# Smartfin_Main_PCBA_Wet_Dry_Sensor.net
KiCad netlist of a schematic drawn in Altium Designer
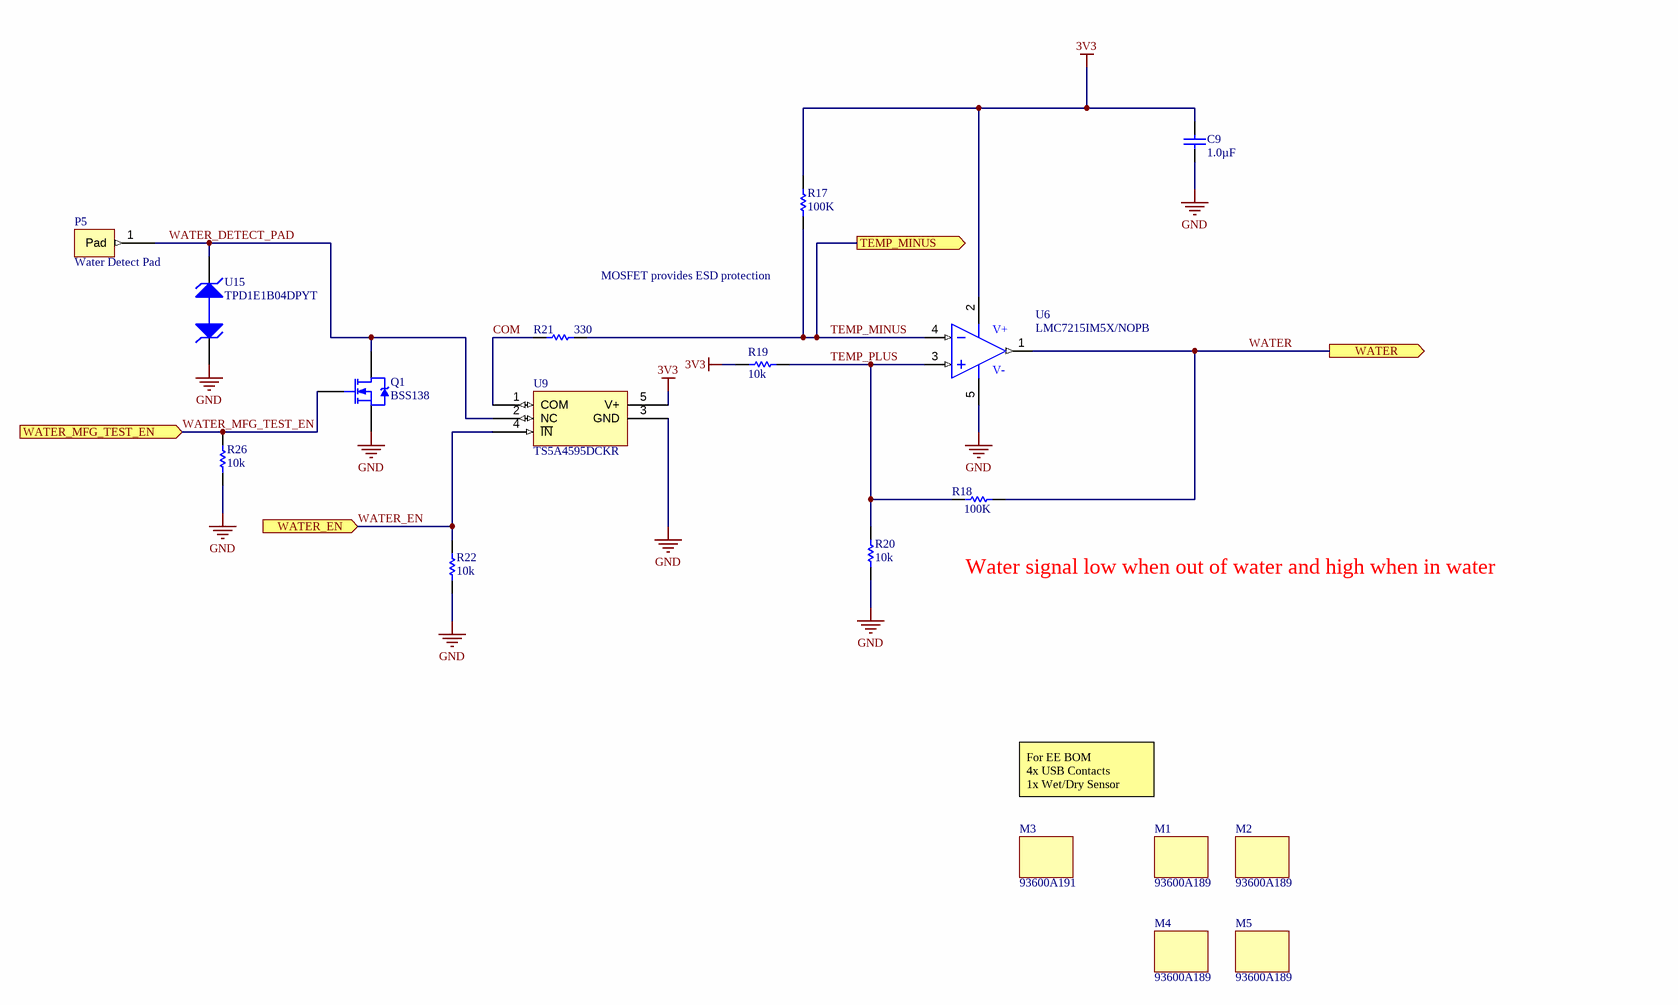
[diagram p0: Smartfin Main PCBA Wet Dry Sensor.SchDoc]

(export (version "E")
  (design (tool "Eeschema 10.0.6"))
  (components
    (comp (ref "C9")
      (value "1.0µF")
      (footprint "CAPC0402(1005)60_N")
      (description "CAP CER 1UF 10V 10% X5R 0402")
      (fields
        (field (name "MANUFACTURER") "Yageo")
        (field (name "MANUFACTURER PART NUMBER") "CC0402KRX5R6BB105")
      )
      (libsource (lib "Syncroness Vault") (part "CAP"))
    )
    (comp (ref "M1")
      (value "93600A189")
      (description "316 Stainless Steel Dowel Pin, 2mm Diameter, 6mm Long")
      (fields (field (name "MANUFACTURER") "McMASTER-Carr"))
      (libsource (lib "Syncroness Vault") (part "93600A156"))
    )
    (comp (ref "M2")
      (value "93600A189")
      (description "316 Stainless Steel Dowel Pin, 2mm Diameter, 6mm Long")
      (fields (field (name "MANUFACTURER") "McMASTER-Carr"))
      (libsource (lib "Syncroness Vault") (part "93600A156"))
    )
    (comp (ref "M3")
      (value "93600A191")
      (description "316 Stainless Steel Dowel Pin, 2mm Diameter, 8mm Long")
      (fields (field (name "MANUFACTURER") "McMASTER-Carr"))
      (libsource (lib "Syncroness Vault") (part "93600A161"))
    )
    (comp (ref "M4")
      (value "93600A189")
      (description "316 Stainless Steel Dowel Pin, 2mm Diameter, 6mm Long")
      (fields (field (name "MANUFACTURER") "McMASTER-Carr"))
      (libsource (lib "Syncroness Vault") (part "93600A156"))
    )
    (comp (ref "M5")
      (value "93600A189")
      (description "316 Stainless Steel Dowel Pin, 2mm Diameter, 6mm Long")
      (fields (field (name "MANUFACTURER") "McMASTER-Carr"))
      (libsource (lib "Syncroness Vault") (part "93600A156"))
    )
    (comp (ref "P5")
      (value "Water Detect Pad")
      (footprint "Water Detect Pad-Footprint-1")
      (libsource (lib "Syncroness Vault") (part "Water Detect Pad"))
    )
    (comp (ref "Q1")
      (value "BSS138")
      (footprint "SOT95P251X112-3N")
      (description "MOSFET N-CH 50V 220MA SOT-23")
      (fields (field (name "MANUFACTURER") "Fairchild Semiconductor"))
      (libsource (lib "Syncroness Vault") (part "NMOS-Power"))
    )
    (comp (ref "R17")
      (value "100K")
      (footprint "RESC1005X04N")
      (description "RES SMD 100K OHM 1% 1/16W 0402")
      (fields
        (field (name "MANUFACTURER") "Vishay Dale")
        (field (name "MANUFACTURER PART NUMBER") "CRCW0402100KFKED")
      )
      (libsource (lib "Syncroness Vault") (part "RES"))
    )
    (comp (ref "R18")
      (value "100K")
      (footprint "RESC1005X04N")
      (description "RES SMD 100K OHM 1% 1/16W 0402")
      (fields
        (field (name "MANUFACTURER") "Vishay Dale")
        (field (name "MANUFACTURER PART NUMBER") "CRCW0402100KFKED")
      )
      (libsource (lib "Syncroness Vault") (part "RES"))
    )
    (comp (ref "R19")
      (value "10k")
      (footprint "RESC0402(1005)_N")
      (description "RES SMD 10K OHM 0.1% 1/16W 0402")
      (fields
        (field (name "TOLERANCE") "±0.1%")
        (field (name "MANUFACTURER") "Panasonic Electronic Components")
      )
      (libsource (lib "Syncroness Vault") (part "RES"))
    )
    (comp (ref "R20")
      (value "10k")
      (footprint "RESC0402(1005)_N")
      (description "RES SMD 10K OHM 0.1% 1/16W 0402")
      (fields
        (field (name "TOLERANCE") "±0.1%")
        (field (name "MANUFACTURER") "Panasonic Electronic Components")
      )
      (libsource (lib "Syncroness Vault") (part "RES"))
    )
    (comp (ref "R21")
      (value "330")
      (footprint "RESC1005X04N")
      (description "RES SMD 330 OHM 1% 1/16W 0402")
      (fields
        (field (name "MANUFACTURER") "Vishay Dale")
        (field (name "MANUFACTURER PART NUMBER") "CRCW0402330RFKED")
      )
      (libsource (lib "Syncroness Vault") (part "RES"))
    )
    (comp (ref "R22")
      (value "10k")
      (footprint "RESC0402(1005)_N")
      (description "RES SMD 10K OHM 0.1% 1/16W 0402")
      (fields
        (field (name "TOLERANCE") "±0.1%")
        (field (name "MANUFACTURER") "Panasonic Electronic Components")
      )
      (libsource (lib "Syncroness Vault") (part "RES"))
    )
    (comp (ref "R26")
      (value "10k")
      (footprint "RESC0402(1005)_N")
      (description "RES SMD 10K OHM 0.1% 1/16W 0402")
      (fields
        (field (name "TOLERANCE") "±0.1%")
        (field (name "MANUFACTURER") "Panasonic Electronic Components")
      )
      (libsource (lib "Syncroness Vault") (part "RES"))
    )
    (comp (ref "U6")
      (value "LMC7215IM5X/NOPB")
      (footprint "LMC7215IM5X_NOPB-Footprint-1")
      (description "Comparator Single 8V 5-Pin SOT-23 T/R")
      (fields (field (name "MANUFACTURER") "Texas Instruments"))
      (libsource (lib "Syncroness Vault") (part "LMC7215IM5X_NOPB"))
    )
    (comp (ref "U9")
      (value "TS5A4595DCKR")
      (footprint "TS5A4595DCKR-Footprint-1")
      (description "IC, ANALOG SWITCH 5V SC70-5")
      (fields (field (name "MANUFACTURER") "Texas Instruments"))
      (libsource (lib "Syncroness Vault") (part "TS5A4595DCKR"))
    )
    (comp (ref "U15")
      (value "TPD1E1B04DPYT")
      (footprint "TPD1E10B06DPYT-Footprint-1")
      (description "TVS DIODE 3.6V 8.5V 2X1SON")
      (fields (field (name "MANUFACTURER") "Texas Instruments"))
      (libsource (lib "Syncroness Vault") (part "TPD1E10B06DPYR"))
    )
  )
  (nets
    (net (code "2") (name "/COM") (class "Default")
      (node (ref "R21") (pin "1") (pinfunction "1_1") (pintype "passive"))
      (node (ref "U9") (pin "1") (pinfunction "COM_1") (pintype "bidirectional"))
    )
    (net (code "3") (name "/TEMP_MINUS") (class "Default")
      (node (ref "R17") (pin "1") (pinfunction "1_1") (pintype "passive"))
      (node (ref "R21") (pin "2") (pinfunction "2_2") (pintype "passive"))
      (node (ref "U6") (pin "4") (pinfunction "IN-_4") (pintype "input"))
    )
    (net (code "4") (name "/TEMP_PLUS") (class "Default")
      (node (ref "R18") (pin "2") (pinfunction "2_2") (pintype "passive"))
      (node (ref "R19") (pin "1") (pinfunction "1_1") (pintype "passive"))
      (node (ref "R20") (pin "2") (pinfunction "2_2") (pintype "passive"))
      (node (ref "U6") (pin "3") (pinfunction "IN+_3") (pintype "input"))
    )
    (net (code "5") (name "/WATER") (class "Default")
      (node (ref "R18") (pin "1") (pinfunction "1_1") (pintype "passive"))
      (node (ref "U6") (pin "1") (pinfunction "OUT_1") (pintype "output"))
    )
    (net (code "6") (name "/WATER_DETECT_PAD") (class "Default")
      (node (ref "P5") (pin "1") (pinfunction "Pad_1") (pintype "output"))
      (node (ref "Q1") (pin "D") (pinfunction "D_D") (pintype "passive"))
      (node (ref "U15") (pin "1") (pinfunction "1_1") (pintype "passive"))
      (node (ref "U9") (pin "2") (pinfunction "NC_2") (pintype "bidirectional"))
    )
    (net (code "7") (name "/WATER_EN") (class "Default")
      (node (ref "R22") (pin "2") (pinfunction "2_2") (pintype "passive"))
      (node (ref "U9") (pin "4") (pinfunction "~{IN}_4") (pintype "input"))
    )
    (net (code "8") (name "/WATER_MFG_TEST_EN") (class "Default")
      (node (ref "Q1") (pin "G") (pinfunction "G_G") (pintype "passive"))
      (node (ref "R26") (pin "2") (pinfunction "2_2") (pintype "passive"))
    )
    (net (code "9") (name "3V3") (class "Default")
      (node (ref "C9") (pin "2") (pinfunction "2_2") (pintype "passive"))
      (node (ref "R17") (pin "2") (pinfunction "2_2") (pintype "passive"))
      (node (ref "R19") (pin "2") (pinfunction "2_2") (pintype "passive"))
      (node (ref "U6") (pin "2") (pinfunction "V+_2") (pintype "power_in"))
      (node (ref "U9") (pin "5") (pinfunction "V+_5") (pintype "power_in"))
    )
    (net (code "10") (name "GND") (class "Default")
      (node (ref "C9") (pin "1") (pinfunction "1_1") (pintype "passive"))
      (node (ref "Q1") (pin "S") (pinfunction "S_S") (pintype "passive"))
      (node (ref "R20") (pin "1") (pinfunction "1_1") (pintype "passive"))
      (node (ref "R22") (pin "1") (pinfunction "1_1") (pintype "passive"))
      (node (ref "R26") (pin "1") (pinfunction "1_1") (pintype "passive"))
      (node (ref "U15") (pin "2") (pinfunction "2_2") (pintype "passive"))
      (node (ref "U6") (pin "5") (pinfunction "V-_5") (pintype "power_in"))
      (node (ref "U9") (pin "3") (pinfunction "GND_3") (pintype "power_in"))
    )
  )
)
